# carcomputer_split1.net
KiCad netlist of a schematic drawn in EAGLE
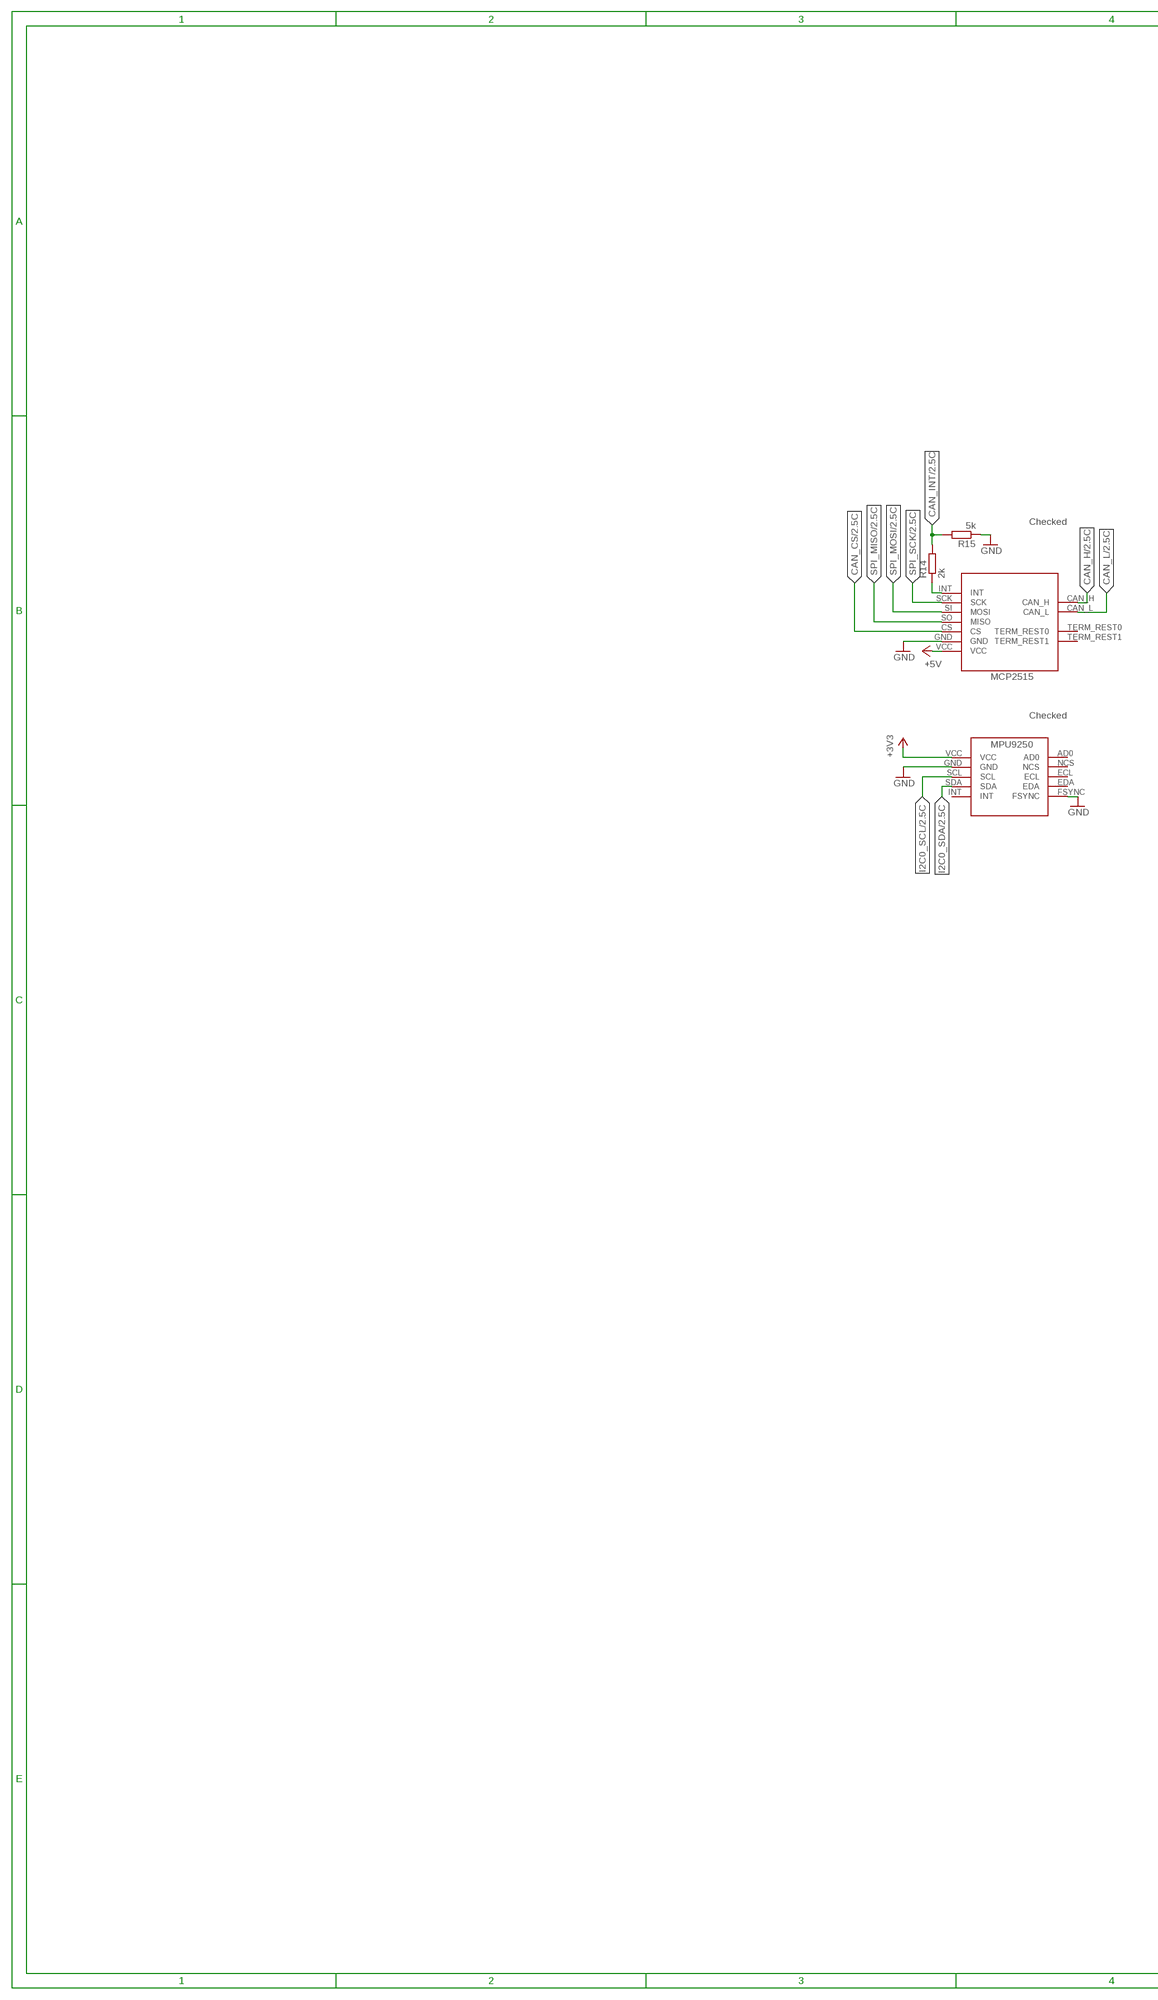
[diagram p0: schematic, sheet 1, part 1 of 2]
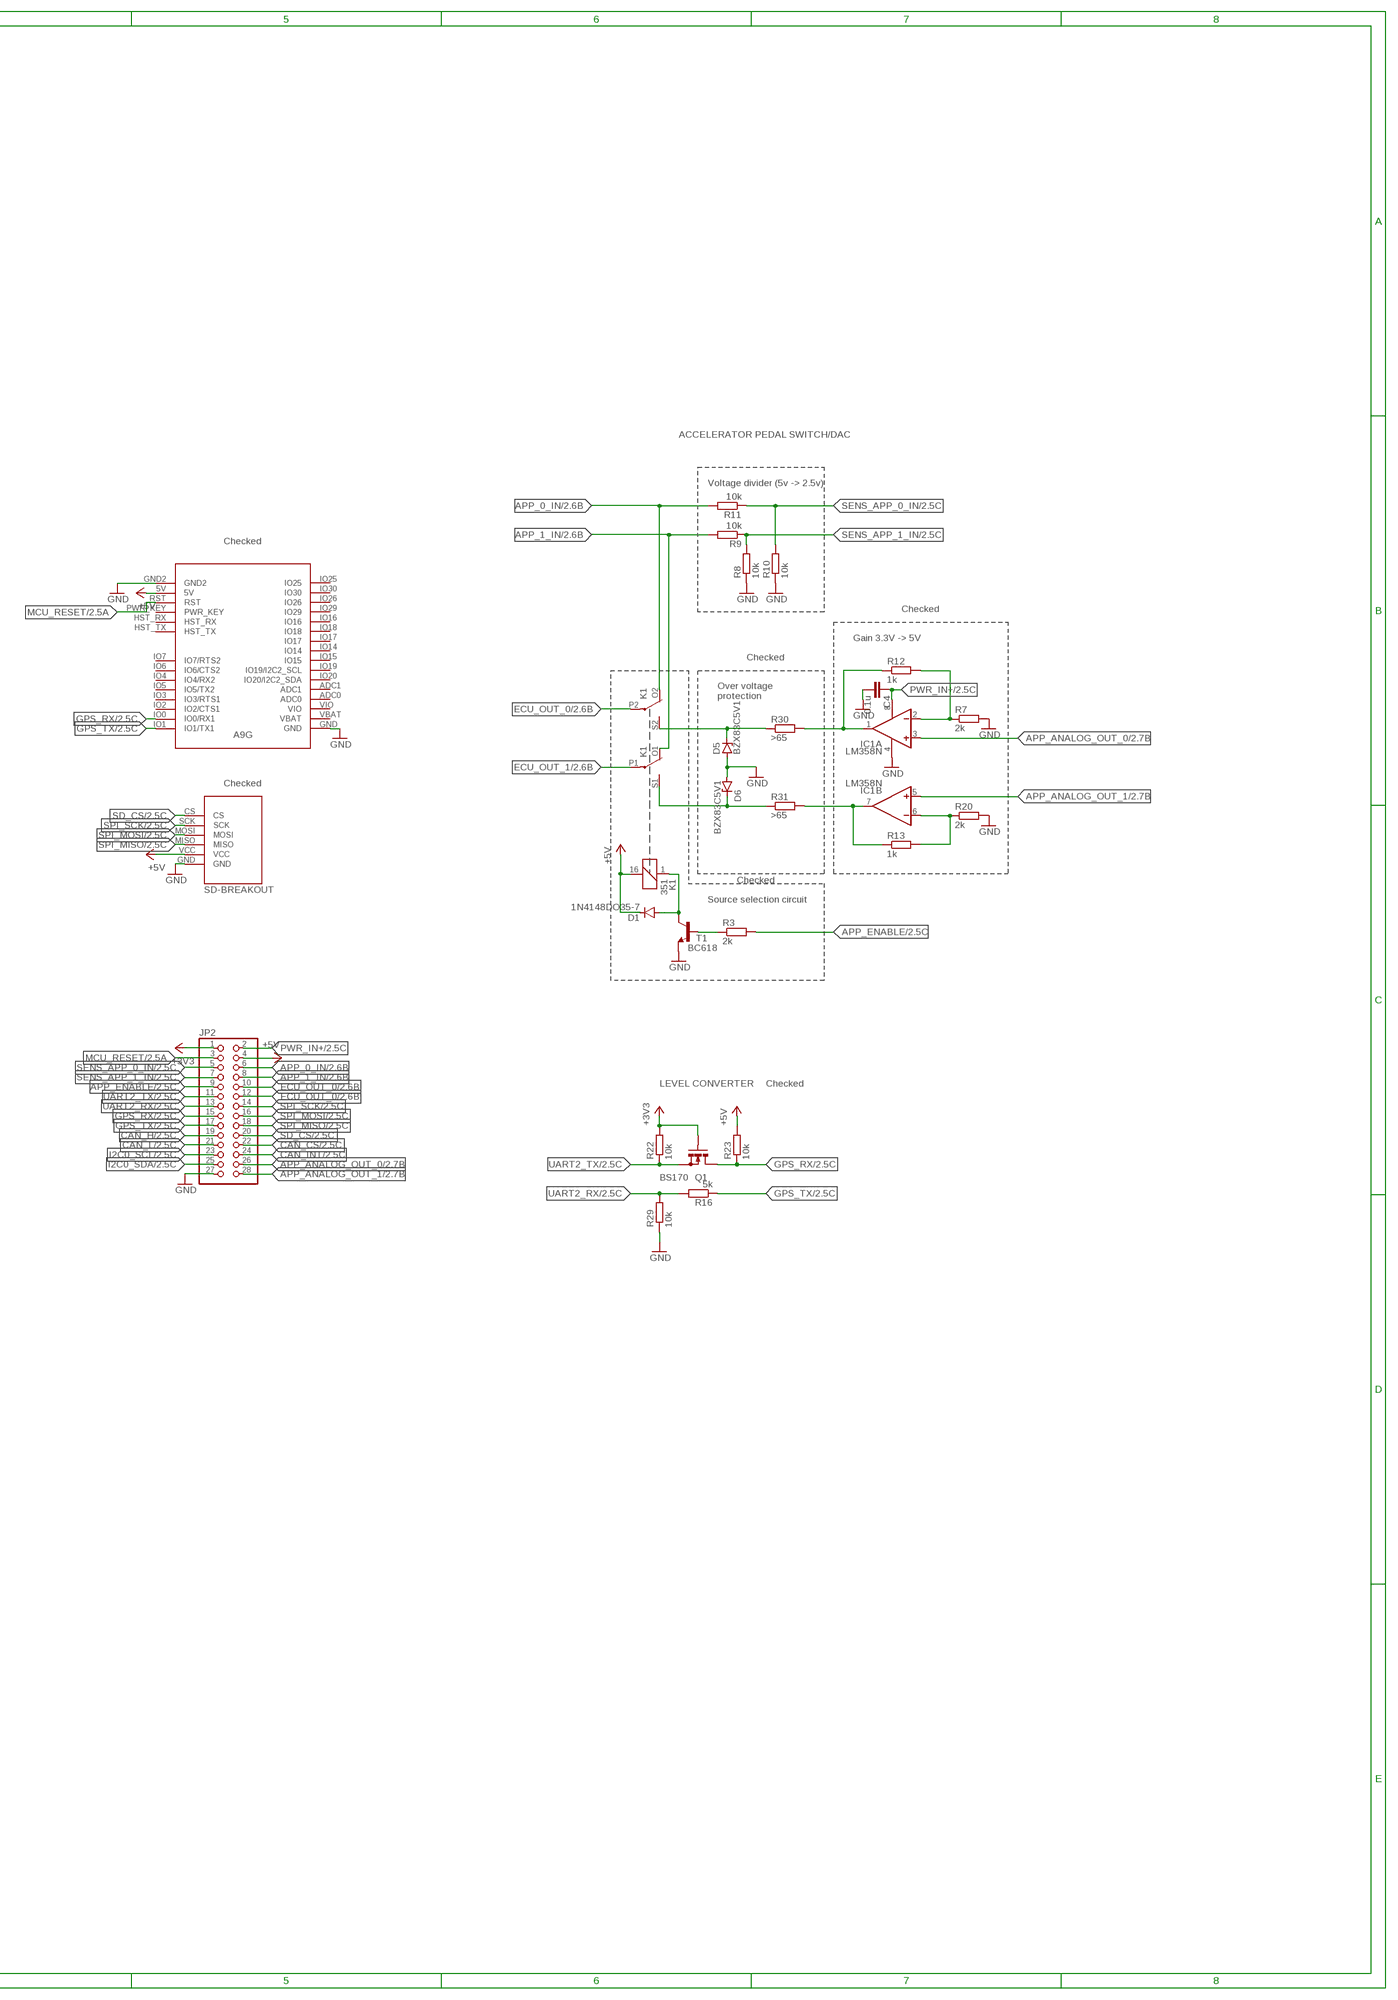
[diagram p1: schematic, sheet 1, part 2 of 2]
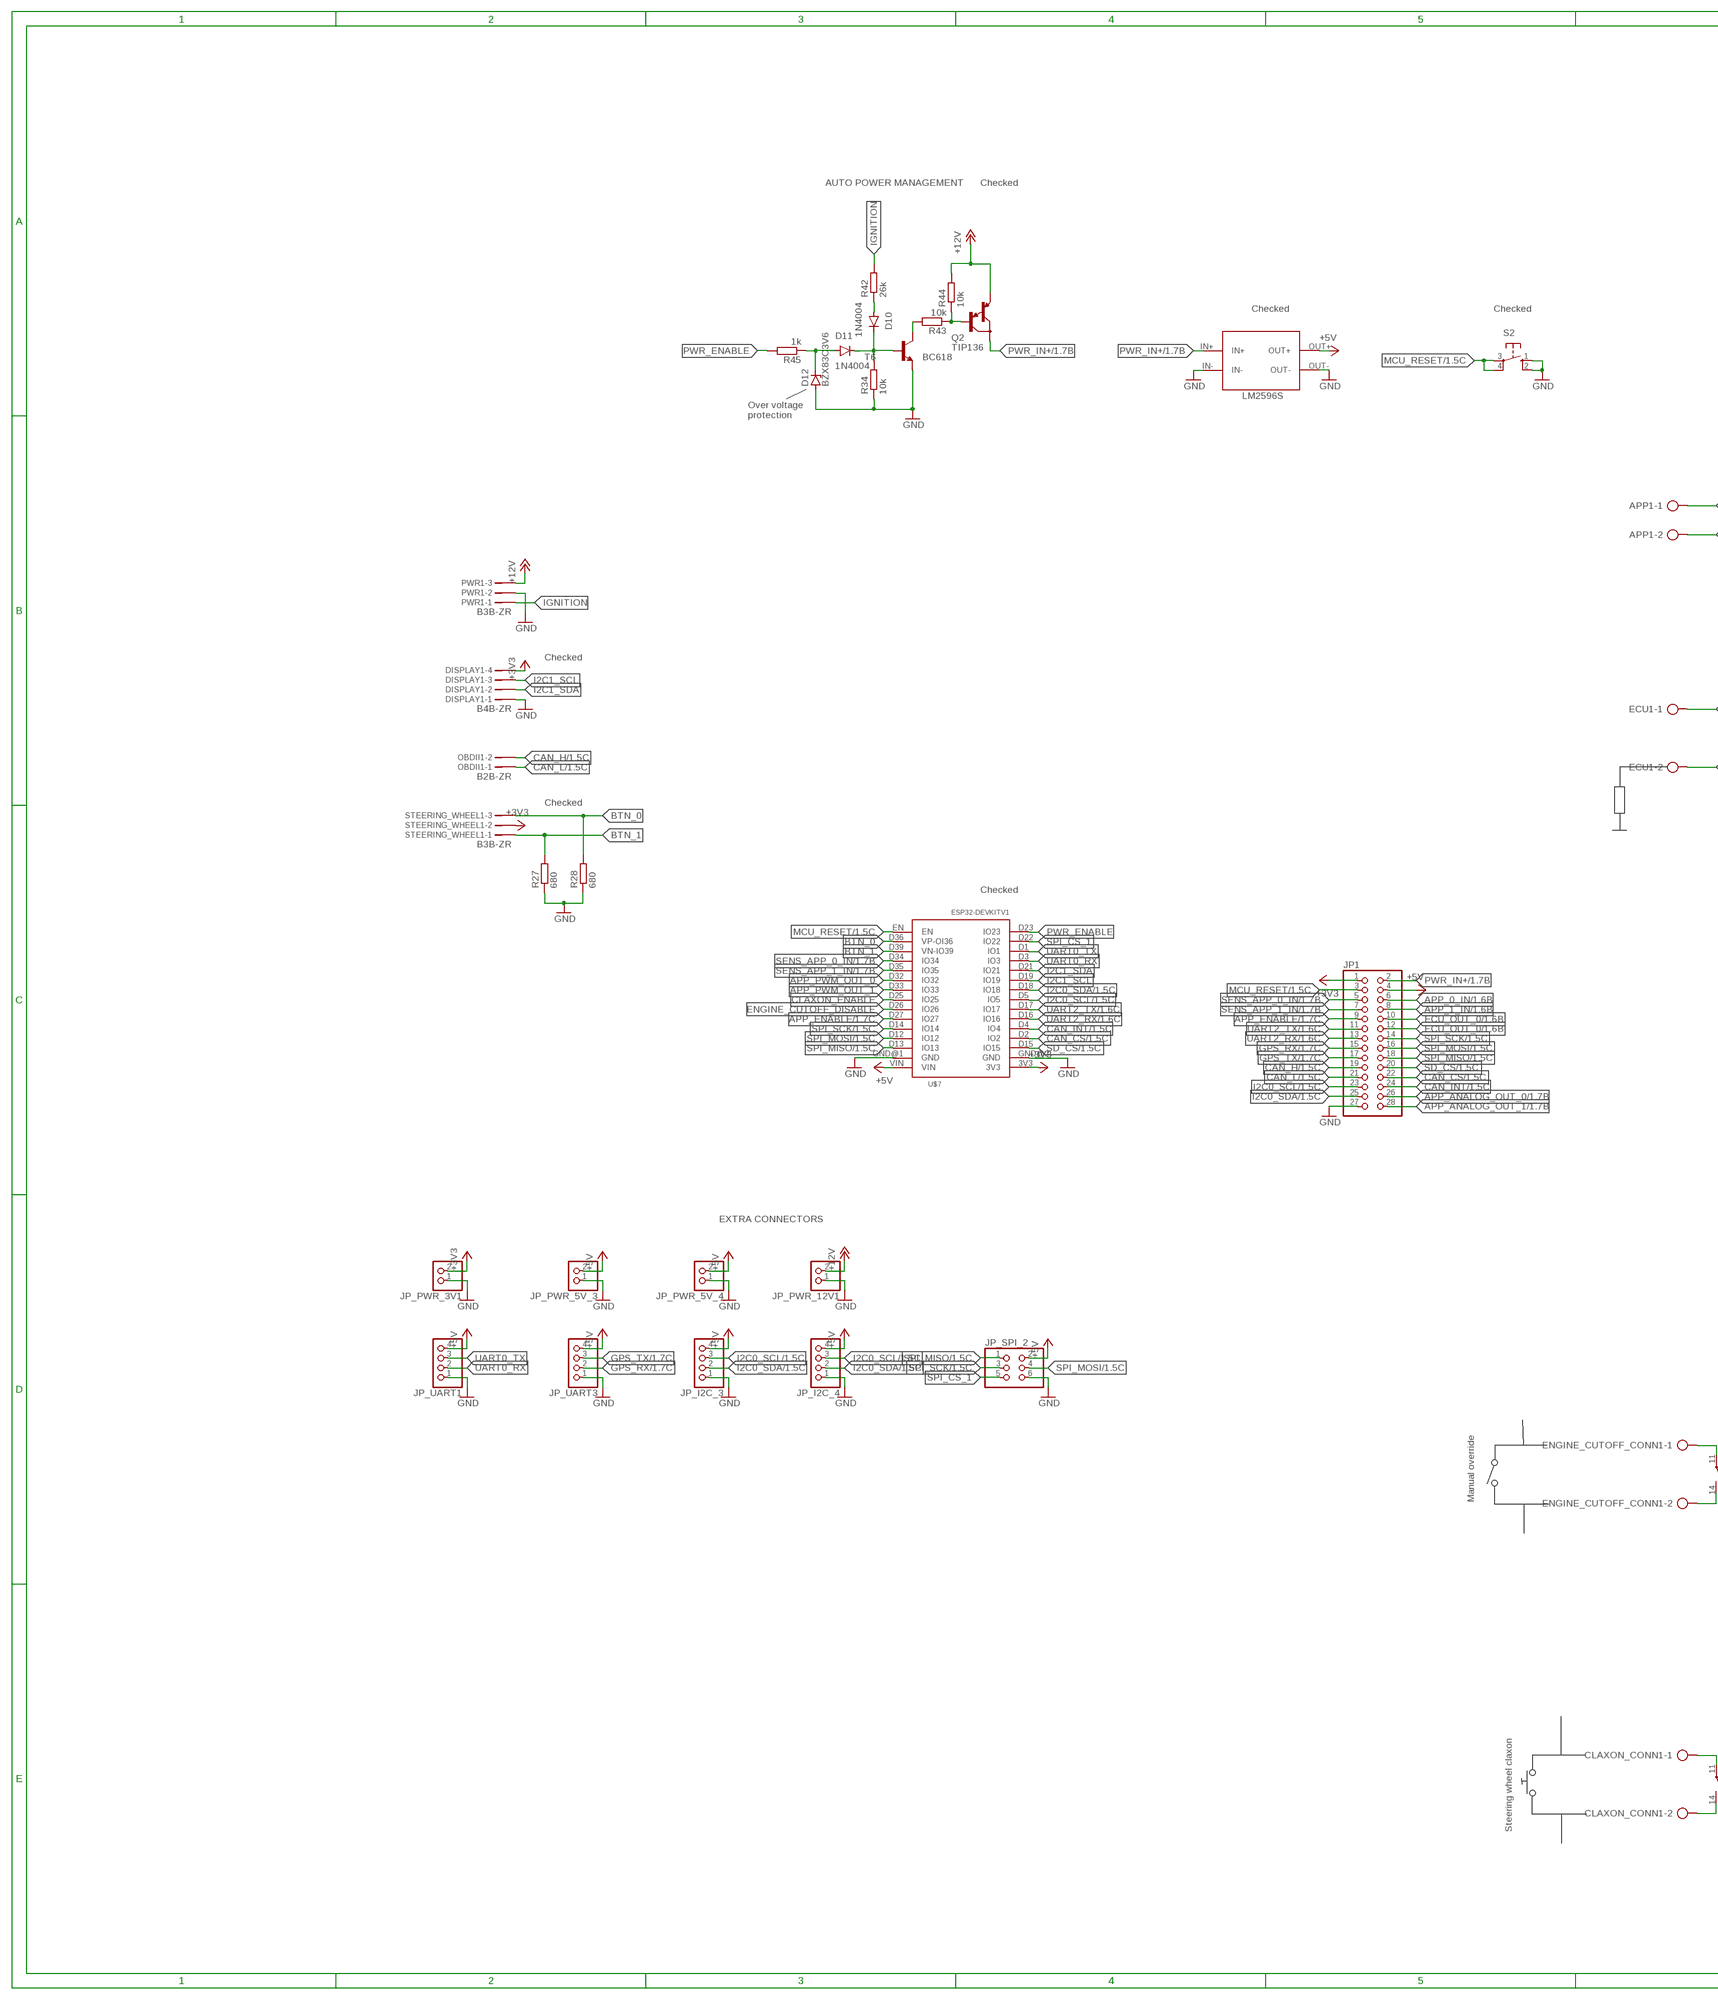
[diagram p2: schematic, sheet 2, part 1 of 2]
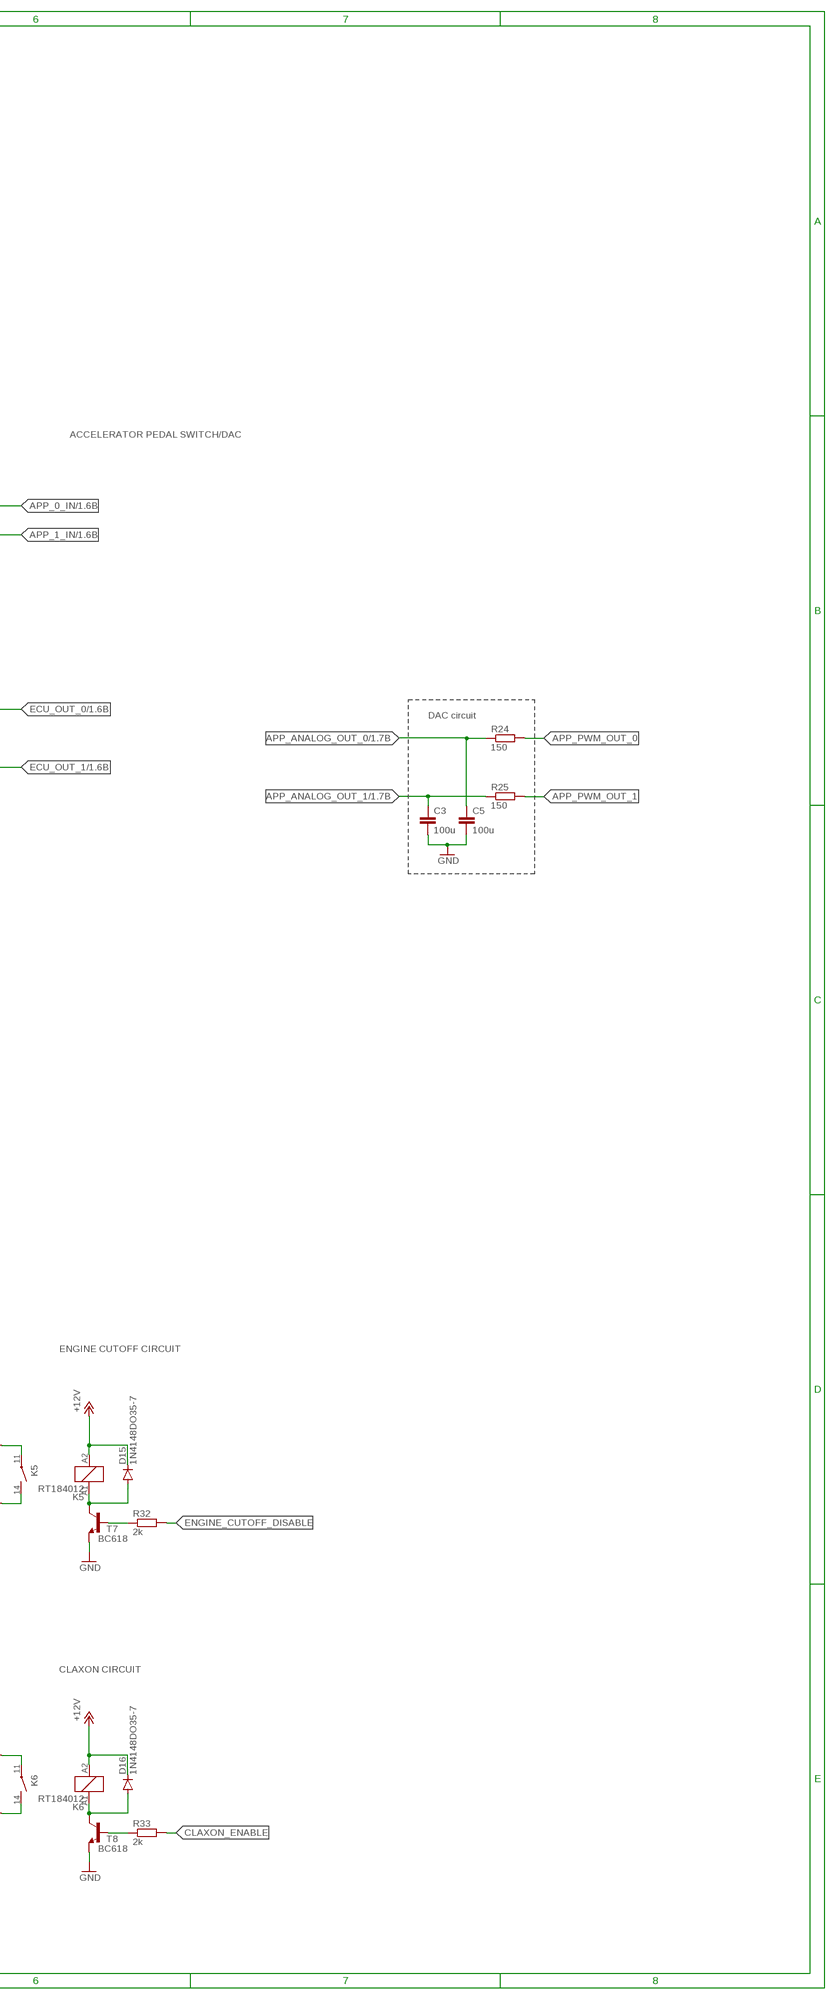
[diagram p3: schematic, sheet 2, part 2 of 2]

(export (version "E")
  (design (tool "Eeschema 10.0.6"))
  (components
    (comp (ref "C4")
      (value "0.1u")
      (footprint "eagle-import:C025-050X050")
      (libsource (lib "eagle-import") (part "C-EU025-050X050"))
    )
    (comp (ref "D1")
      (value "1N4148DO35-7")
      (footprint "eagle-import:DO35-7")
      (libsource (lib "eagle-import") (part "1N4148DO35-7"))
    )
    (comp (ref "D5")
      (value "BZX83C5V1")
      (footprint "eagle-import:DO41Z10")
      (libsource (lib "eagle-import") (part "BZX85"))
    )
    (comp (ref "D6")
      (value "BZX83C5V1")
      (footprint "eagle-import:DO41Z10")
      (libsource (lib "eagle-import") (part "BZX85"))
    )
    (comp (ref "IC1")
      (value "LM358N")
      (footprint "eagle-import:DIL08")
      (libsource (lib "eagle-import") (part "LM358N"))
    )
    (comp (ref "JP2")
      (value "PINHD-2X14")
      (footprint "eagle-import:2X14")
      (libsource (lib "eagle-import") (part "PINHD-2X14"))
    )
    (comp (ref "K1")
      (value "351")
      (footprint "eagle-import:351")
      (libsource (lib "eagle-import") (part "351"))
    )
    (comp (ref "Q1")
      (value "BS170")
      (footprint "eagle-import:SOT54E")
      (libsource (lib "eagle-import") (part "BS170"))
    )
    (comp (ref "R3")
      (value "2k")
      (footprint "eagle-import:0207_7")
      (libsource (lib "eagle-import") (part "R-EU_0207/7"))
    )
    (comp (ref "R7")
      (value "2k")
      (footprint "eagle-import:0207_7")
      (libsource (lib "eagle-import") (part "R-EU_0207/7"))
    )
    (comp (ref "R8")
      (value "10k")
      (footprint "eagle-import:0207_7")
      (libsource (lib "eagle-import") (part "R-EU_0207/7"))
    )
    (comp (ref "R9")
      (value "10k")
      (footprint "eagle-import:0207_7")
      (libsource (lib "eagle-import") (part "R-EU_0207/7"))
    )
    (comp (ref "R10")
      (value "10k")
      (footprint "eagle-import:0207_7")
      (libsource (lib "eagle-import") (part "R-EU_0207/7"))
    )
    (comp (ref "R11")
      (value "10k")
      (footprint "eagle-import:0207_7")
      (libsource (lib "eagle-import") (part "R-EU_0207/7"))
    )
    (comp (ref "R12")
      (value "1k")
      (footprint "eagle-import:0207_7")
      (libsource (lib "eagle-import") (part "R-EU_0207/7"))
    )
    (comp (ref "R13")
      (value "1k")
      (footprint "eagle-import:0207_7")
      (libsource (lib "eagle-import") (part "R-EU_0207/7"))
    )
    (comp (ref "R14")
      (value "2k")
      (footprint "eagle-import:0207_7")
      (libsource (lib "eagle-import") (part "R-EU_0207/7"))
    )
    (comp (ref "R15")
      (value "5k")
      (footprint "eagle-import:0207_7")
      (libsource (lib "eagle-import") (part "R-EU_0207/7"))
    )
    (comp (ref "R16")
      (value "5k")
      (footprint "eagle-import:0207_7")
      (libsource (lib "eagle-import") (part "R-EU_0207/7"))
    )
    (comp (ref "R20")
      (value "2k")
      (footprint "eagle-import:0207_7")
      (libsource (lib "eagle-import") (part "R-EU_0207/7"))
    )
    (comp (ref "R22")
      (value "10k")
      (footprint "eagle-import:0207_7")
      (libsource (lib "eagle-import") (part "R-EU_0207/7"))
    )
    (comp (ref "R23")
      (value "10k")
      (footprint "eagle-import:0207_7")
      (libsource (lib "eagle-import") (part "R-EU_0207/7"))
    )
    (comp (ref "R29")
      (value "10k")
      (footprint "eagle-import:0207_7")
      (libsource (lib "eagle-import") (part "R-EU_0207/7"))
    )
    (comp (ref "R30")
      (value ">65")
      (footprint "eagle-import:0207_7")
      (libsource (lib "eagle-import") (part "R-EU_0207/7"))
    )
    (comp (ref "R31")
      (value ">65")
      (footprint "eagle-import:0207_7")
      (libsource (lib "eagle-import") (part "R-EU_0207/7"))
    )
    (comp (ref "T1")
      (value "BC618")
      (footprint "eagle-import:TO92-EBC")
      (libsource (lib "eagle-import") (part "BC618"))
    )
    (comp (ref "U$2")
      (value "MCP2515_DEVBOARDINVERTED")
      (footprint "eagle-import:MCP2515_DEVBOARD_INVERTED")
      (libsource (lib "eagle-import") (part "MCP2515_DEVBOARDINVERTED"))
    )
    (comp (ref "U$3")
      (value "MPU9250_BREAKOUT")
      (footprint "eagle-import:MPU9250_BREAKOUT")
      (libsource (lib "eagle-import") (part "MPU9250_BREAKOUT"))
    )
    (comp (ref "U$5")
      (value "HKD-MICRO-SD-BREAKOUT")
      (footprint "eagle-import:HKD-MICRO-SD-BREAKOUT")
      (libsource (lib "eagle-import") (part "HKD-MICRO-SD-BREAKOUT"))
    )
    (comp (ref "U$6")
      (value "A9G")
      (footprint "eagle-import:A9G")
      (libsource (lib "eagle-import") (part "A9G"))
    )
    (comp (ref "APP1")
      (value "AK300/2")
      (footprint "eagle-import:AK300_2")
      (libsource (lib "eagle-import") (part "AK300/2"))
    )
    (comp (ref "C3")
      (value "100u")
      (footprint "eagle-import:C025-050X050")
      (libsource (lib "eagle-import") (part "C-EU025-050X050"))
    )
    (comp (ref "C5")
      (value "100u")
      (footprint "eagle-import:C025-050X050")
      (libsource (lib "eagle-import") (part "C-EU025-050X050"))
    )
    (comp (ref "CLAXON_CONN1")
      (value "AK300/2")
      (footprint "eagle-import:AK300_2")
      (libsource (lib "eagle-import") (part "AK300/2"))
    )
    (comp (ref "D10")
      (value "1N4004")
      (footprint "eagle-import:DO41-10")
      (libsource (lib "eagle-import") (part "1N4004"))
    )
    (comp (ref "D11")
      (value "1N4004")
      (footprint "eagle-import:DO41-10")
      (libsource (lib "eagle-import") (part "1N4004"))
    )
    (comp (ref "D12")
      (value "BZX83C3V6")
      (footprint "eagle-import:DO41Z10")
      (libsource (lib "eagle-import") (part "BZX85"))
    )
    (comp (ref "D15")
      (value "1N4148DO35-7")
      (footprint "eagle-import:DO35-7")
      (libsource (lib "eagle-import") (part "1N4148DO35-7"))
    )
    (comp (ref "D16")
      (value "1N4148DO35-7")
      (footprint "eagle-import:DO35-7")
      (libsource (lib "eagle-import") (part "1N4148DO35-7"))
    )
    (comp (ref "DISPLAY1")
      (value "B4B-ZR")
      (footprint "eagle-import:B4B-ZR")
      (fields (field (name "MF") "FARNELL") (field (name "MPN") "B4B-ZR(LF)(SN)"))
      (libsource (lib "eagle-import") (part "?4B-ZRB"))
    )
    (comp (ref "ECU1")
      (value "AK300/2")
      (footprint "eagle-import:AK300_2")
      (libsource (lib "eagle-import") (part "AK300/2"))
    )
    (comp (ref "ENGINE_CUTOFF_CONN1")
      (value "AK300/2")
      (footprint "eagle-import:AK300_2")
      (libsource (lib "eagle-import") (part "AK300/2"))
    )
    (comp (ref "JP1")
      (value "PINHD-2X14")
      (footprint "eagle-import:2X14")
      (libsource (lib "eagle-import") (part "PINHD-2X14"))
    )
    (comp (ref "JP_I2C_3")
      (value "PINHD-1X4")
      (footprint "eagle-import:1X04")
      (libsource (lib "eagle-import") (part "PINHD-1X4"))
    )
    (comp (ref "JP_I2C_4")
      (value "PINHD-1X4")
      (footprint "eagle-import:1X04")
      (libsource (lib "eagle-import") (part "PINHD-1X4"))
    )
    (comp (ref "JP_PWR_3V1")
      (value "PINHD-1X2")
      (footprint "eagle-import:1X02")
      (libsource (lib "eagle-import") (part "PINHD-1X2"))
    )
    (comp (ref "JP_PWR_5V_3")
      (value "PINHD-1X2")
      (footprint "eagle-import:1X02")
      (libsource (lib "eagle-import") (part "PINHD-1X2"))
    )
    (comp (ref "JP_PWR_5V_4")
      (value "PINHD-1X2")
      (footprint "eagle-import:1X02")
      (libsource (lib "eagle-import") (part "PINHD-1X2"))
    )
    (comp (ref "JP_PWR_12V1")
      (value "PINHD-1X2")
      (footprint "eagle-import:1X02")
      (libsource (lib "eagle-import") (part "PINHD-1X2"))
    )
    (comp (ref "JP_SPI_2")
      (value "PINHD-2X3")
      (footprint "eagle-import:2X03")
      (libsource (lib "eagle-import") (part "PINHD-2X3"))
    )
    (comp (ref "JP_UART1")
      (value "PINHD-1X4")
      (footprint "eagle-import:1X04")
      (libsource (lib "eagle-import") (part "PINHD-1X4"))
    )
    (comp (ref "JP_UART3")
      (value "PINHD-1X4")
      (footprint "eagle-import:1X04")
      (libsource (lib "eagle-import") (part "PINHD-1X4"))
    )
    (comp (ref "K5")
      (value "RT184012")
      (footprint "eagle-import:RT-N_O12A3.5")
      (fields (field (name "MF") "TYCO ELECTRONICS"))
      (libsource (lib "eagle-import") (part "RT?184012"))
    )
    (comp (ref "K6")
      (value "RT184012")
      (footprint "eagle-import:RT-N_O12A3.5")
      (fields (field (name "MF") "TYCO ELECTRONICS"))
      (libsource (lib "eagle-import") (part "RT?184012"))
    )
    (comp (ref "OBDII1")
      (value "B2B-ZR")
      (footprint "eagle-import:B2B-ZR")
      (libsource (lib "eagle-import") (part "?2B-ZRB"))
    )
    (comp (ref "PWR1")
      (value "B3B-ZR")
      (footprint "eagle-import:B3B-ZR")
      (libsource (lib "eagle-import") (part "?3B-ZRB"))
    )
    (comp (ref "Q2")
      (value "TIP136")
      (footprint "eagle-import:TO220")
      (libsource (lib "eagle-import") (part "TIP136"))
    )
    (comp (ref "R24")
      (value "150")
      (footprint "eagle-import:0207_7")
      (libsource (lib "eagle-import") (part "R-EU_0207/7"))
    )
    (comp (ref "R25")
      (value "150")
      (footprint "eagle-import:0207_7")
      (libsource (lib "eagle-import") (part "R-EU_0207/7"))
    )
    (comp (ref "R27")
      (value "680")
      (footprint "eagle-import:0207_7")
      (libsource (lib "eagle-import") (part "R-EU_0207/7"))
    )
    (comp (ref "R28")
      (value "680")
      (footprint "eagle-import:0207_7")
      (libsource (lib "eagle-import") (part "R-EU_0207/7"))
    )
    (comp (ref "R32")
      (value "2k")
      (footprint "eagle-import:0207_7")
      (libsource (lib "eagle-import") (part "R-EU_0207/7"))
    )
    (comp (ref "R33")
      (value "2k")
      (footprint "eagle-import:0207_7")
      (libsource (lib "eagle-import") (part "R-EU_0207/7"))
    )
    (comp (ref "R34")
      (value "10k")
      (footprint "eagle-import:0207_7")
      (libsource (lib "eagle-import") (part "R-EU_0207/7"))
    )
    (comp (ref "R42")
      (value "26k")
      (footprint "eagle-import:0207_7")
      (libsource (lib "eagle-import") (part "R-EU_0207/7"))
    )
    (comp (ref "R43")
      (value "10k")
      (footprint "eagle-import:0207_7")
      (libsource (lib "eagle-import") (part "R-EU_0207/7"))
    )
    (comp (ref "R44")
      (value "10k")
      (footprint "eagle-import:0207_7")
      (libsource (lib "eagle-import") (part "R-EU_0207/7"))
    )
    (comp (ref "R45")
      (value "1k")
      (footprint "eagle-import:0207_7")
      (libsource (lib "eagle-import") (part "R-EU_0207/7"))
    )
    (comp (ref "S2")
      (value "10-XX")
      (footprint "eagle-import:B3F-10XX")
      (fields (field (name "MPN") "B3F-1000"))
      (libsource (lib "eagle-import") (part "10-XX"))
    )
    (comp (ref "STEERING_WHEEL1")
      (value "B3B-ZR")
      (footprint "eagle-import:B3B-ZR")
      (libsource (lib "eagle-import") (part "?3B-ZRB"))
    )
    (comp (ref "T6")
      (value "BC618")
      (footprint "eagle-import:TO92-EBC")
      (libsource (lib "eagle-import") (part "BC618"))
    )
    (comp (ref "T7")
      (value "BC618")
      (footprint "eagle-import:TO92-EBC")
      (libsource (lib "eagle-import") (part "BC618"))
    )
    (comp (ref "T8")
      (value "BC618")
      (footprint "eagle-import:TO92-EBC")
      (libsource (lib "eagle-import") (part "BC618"))
    )
    (comp (ref "U$7")
      (value "ESP32DEVKITV1")
      (footprint "eagle-import:ESP32-DEVKITV1")
      (libsource (lib "eagle-import") (part "ESP32DEVKITV1"))
    )
    (comp (ref "U$10")
      (value "LM2596S")
      (footprint "eagle-import:LM2596S")
      (libsource (lib "eagle-import") (part "LM2596S"))
    )
  )
  (nets
    (net (code "1") (name "+3V3") (class "Default")
      (node (ref "DISPLAY1") (pin "4") (pinfunction "1_4") (pintype "passive"))
      (node (ref "JP1") (pin "1") (pinfunction "1_1") (pintype "passive"))
      (node (ref "JP2") (pin "1") (pinfunction "1_1") (pintype "passive"))
      (node (ref "JP_PWR_3V1") (pin "2") (pinfunction "2_2") (pintype "passive"))
      (node (ref "Q1") (pin "G") (pinfunction "G_G") (pintype "passive"))
      (node (ref "R22") (pin "2") (pinfunction "2_2") (pintype "passive"))
      (node (ref "STEERING_WHEEL1") (pin "2") (pinfunction "1_2") (pintype "passive"))
      (node (ref "U$3") (pin "VCC") (pinfunction "VCC_VCC") (pintype "bidirectional"))
      (node (ref "U$7") (pin "3V3") (pinfunction "3V3_3V3") (pintype "bidirectional"))
    )
    (net (code "2") (name "+5V") (class "Default")
      (node (ref "D1") (pin "C") (pinfunction "C_C") (pintype "passive"))
      (node (ref "JP1") (pin "4") (pinfunction "4_4") (pintype "passive"))
      (node (ref "JP2") (pin "4") (pinfunction "4_4") (pintype "passive"))
      (node (ref "JP_I2C_3") (pin "4") (pinfunction "4_4") (pintype "passive"))
      (node (ref "JP_I2C_4") (pin "4") (pinfunction "4_4") (pintype "passive"))
      (node (ref "JP_PWR_5V_3") (pin "2") (pinfunction "2_2") (pintype "passive"))
      (node (ref "JP_PWR_5V_4") (pin "2") (pinfunction "2_2") (pintype "passive"))
      (node (ref "JP_SPI_2") (pin "2") (pinfunction "2_2") (pintype "passive"))
      (node (ref "JP_UART1") (pin "4") (pinfunction "4_4") (pintype "passive"))
      (node (ref "JP_UART3") (pin "4") (pinfunction "4_4") (pintype "passive"))
      (node (ref "K1") (pin "16") (pinfunction "2_16") (pintype "passive"))
      (node (ref "R23") (pin "2") (pinfunction "2_2") (pintype "passive"))
      (node (ref "U$10") (pin "OUT+") (pinfunction "OUT+_OUT+") (pintype "bidirectional"))
      (node (ref "U$2") (pin "VCC") (pinfunction "VCC_VCC") (pintype "bidirectional"))
      (node (ref "U$5") (pin "VCC") (pinfunction "VCC_VCC") (pintype "bidirectional"))
      (node (ref "U$6") (pin "5V") (pinfunction "5V_5V") (pintype "bidirectional"))
      (node (ref "U$7") (pin "VIN") (pinfunction "VIN_VIN") (pintype "bidirectional"))
    )
    (net (code "3") (name "+12V") (class "Default")
      (node (ref "D15") (pin "C") (pinfunction "C_C") (pintype "passive"))
      (node (ref "D16") (pin "C") (pinfunction "C_C") (pintype "passive"))
      (node (ref "JP_PWR_12V1") (pin "2") (pinfunction "2_2") (pintype "passive"))
      (node (ref "K5") (pin "A2") (pinfunction "2_A2") (pintype "passive"))
      (node (ref "K6") (pin "A2") (pinfunction "2_A2") (pintype "passive"))
      (node (ref "PWR1") (pin "3") (pinfunction "1_3") (pintype "passive"))
      (node (ref "Q2") (pin "3") (pinfunction "E_3") (pintype "passive"))
      (node (ref "R44") (pin "2") (pinfunction "2_2") (pintype "passive"))
    )
    (net (code "4") (name "APP_0_IN") (class "Default")
      (node (ref "APP1") (pin "1") (pinfunction "KL_1") (pintype "passive"))
      (node (ref "JP1") (pin "6") (pinfunction "6_6") (pintype "passive"))
      (node (ref "JP2") (pin "6") (pinfunction "6_6") (pintype "passive"))
      (node (ref "K1") (pin "O2") (pinfunction "O_O2") (pintype "passive"))
      (node (ref "R11") (pin "2") (pinfunction "2_2") (pintype "passive"))
    )
    (net (code "5") (name "APP_1_IN") (class "Default")
      (node (ref "APP1") (pin "2") (pinfunction "KL_2") (pintype "passive"))
      (node (ref "JP1") (pin "8") (pinfunction "8_8") (pintype "passive"))
      (node (ref "JP2") (pin "8") (pinfunction "8_8") (pintype "passive"))
      (node (ref "K1") (pin "O1") (pinfunction "O_O1") (pintype "passive"))
      (node (ref "R9") (pin "2") (pinfunction "2_2") (pintype "passive"))
    )
    (net (code "6") (name "APP_ANALOG_OUT_0") (class "Default")
      (node (ref "C5") (pin "1") (pinfunction "1_1") (pintype "passive"))
      (node (ref "IC1") (pin "3") (pinfunction "+IN_3") (pintype "input"))
      (node (ref "JP1") (pin "26") (pinfunction "26_26") (pintype "passive"))
      (node (ref "JP2") (pin "26") (pinfunction "26_26") (pintype "passive"))
      (node (ref "R24") (pin "1") (pinfunction "1_1") (pintype "passive"))
    )
    (net (code "7") (name "APP_ANALOG_OUT_1") (class "Default")
      (node (ref "C3") (pin "1") (pinfunction "1_1") (pintype "passive"))
      (node (ref "IC1") (pin "5") (pinfunction "+IN_5") (pintype "input"))
      (node (ref "JP1") (pin "28") (pinfunction "28_28") (pintype "passive"))
      (node (ref "JP2") (pin "28") (pinfunction "28_28") (pintype "passive"))
      (node (ref "R25") (pin "1") (pinfunction "1_1") (pintype "passive"))
    )
    (net (code "8") (name "APP_ENABLE") (class "Default")
      (node (ref "JP1") (pin "9") (pinfunction "9_9") (pintype "passive"))
      (node (ref "JP2") (pin "9") (pinfunction "9_9") (pintype "passive"))
      (node (ref "R3") (pin "2") (pinfunction "2_2") (pintype "passive"))
      (node (ref "U$7") (pin "D27") (pinfunction "IO27_D27") (pintype "bidirectional"))
    )
    (net (code "9") (name "APP_PWM_OUT_0") (class "Default")
      (node (ref "R24") (pin "2") (pinfunction "2_2") (pintype "passive"))
      (node (ref "U$7") (pin "D32") (pinfunction "IO32_D32") (pintype "bidirectional"))
    )
    (net (code "10") (name "APP_PWM_OUT_1") (class "Default")
      (node (ref "R25") (pin "2") (pinfunction "2_2") (pintype "passive"))
      (node (ref "U$7") (pin "D33") (pinfunction "IO33_D33") (pintype "bidirectional"))
    )
    (net (code "11") (name "BTN_0") (class "Default")
      (node (ref "R28") (pin "2") (pinfunction "2_2") (pintype "passive"))
      (node (ref "STEERING_WHEEL1") (pin "3") (pinfunction "1_3") (pintype "passive"))
      (node (ref "U$7") (pin "D36") (pinfunction "VP-OI36_D36") (pintype "bidirectional"))
    )
    (net (code "12") (name "BTN_1") (class "Default")
      (node (ref "R27") (pin "2") (pinfunction "2_2") (pintype "passive"))
      (node (ref "STEERING_WHEEL1") (pin "1") (pinfunction "1_1") (pintype "passive"))
      (node (ref "U$7") (pin "D39") (pinfunction "VN-IO39_D39") (pintype "bidirectional"))
    )
    (net (code "13") (name "CAN_CS") (class "Default")
      (node (ref "JP1") (pin "22") (pinfunction "22_22") (pintype "passive"))
      (node (ref "JP2") (pin "22") (pinfunction "22_22") (pintype "passive"))
      (node (ref "U$2") (pin "CS") (pinfunction "CS_CS") (pintype "input"))
      (node (ref "U$7") (pin "D2") (pinfunction "IO2_D2") (pintype "bidirectional"))
    )
    (net (code "14") (name "CAN_H") (class "Default")
      (node (ref "JP1") (pin "19") (pinfunction "19_19") (pintype "passive"))
      (node (ref "JP2") (pin "19") (pinfunction "19_19") (pintype "passive"))
      (node (ref "OBDII1") (pin "2") (pinfunction "1_2") (pintype "passive"))
      (node (ref "U$2") (pin "CAN_H") (pinfunction "CAN_H_CAN_H") (pintype "bidirectional"))
    )
    (net (code "15") (name "CAN_INT") (class "Default")
      (node (ref "JP1") (pin "24") (pinfunction "24_24") (pintype "passive"))
      (node (ref "JP2") (pin "24") (pinfunction "24_24") (pintype "passive"))
      (node (ref "R14") (pin "2") (pinfunction "2_2") (pintype "passive"))
      (node (ref "R15") (pin "2") (pinfunction "2_2") (pintype "passive"))
      (node (ref "U$7") (pin "D4") (pinfunction "IO4_D4") (pintype "bidirectional"))
    )
    (net (code "16") (name "CAN_L") (class "Default")
      (node (ref "JP1") (pin "21") (pinfunction "21_21") (pintype "passive"))
      (node (ref "JP2") (pin "21") (pinfunction "21_21") (pintype "passive"))
      (node (ref "OBDII1") (pin "1") (pinfunction "1_1") (pintype "passive"))
      (node (ref "U$2") (pin "CAN_L") (pinfunction "CAN_L_CAN_L") (pintype "bidirectional"))
    )
    (net (code "17") (name "CLAXON_ENABLE") (class "Default")
      (node (ref "R33") (pin "2") (pinfunction "2_2") (pintype "passive"))
      (node (ref "U$7") (pin "D25") (pinfunction "IO25_D25") (pintype "bidirectional"))
    )
    (net (code "18") (name "ECU_OUT_0") (class "Default")
      (node (ref "ECU1") (pin "1") (pinfunction "KL_1") (pintype "passive"))
      (node (ref "JP1") (pin "10") (pinfunction "10_10") (pintype "passive"))
      (node (ref "JP1") (pin "12") (pinfunction "12_12") (pintype "passive"))
      (node (ref "JP2") (pin "10") (pinfunction "10_10") (pintype "passive"))
      (node (ref "JP2") (pin "12") (pinfunction "12_12") (pintype "passive"))
      (node (ref "K1") (pin "P2") (pinfunction "P_P2") (pintype "passive"))
    )
    (net (code "19") (name "ECU_OUT_1") (class "Default")
      (node (ref "ECU1") (pin "2") (pinfunction "KL_2") (pintype "passive"))
      (node (ref "K1") (pin "P1") (pinfunction "P_P1") (pintype "passive"))
    )
    (net (code "20") (name "ENGINE_CUTOFF_DISABLE") (class "Default")
      (node (ref "R32") (pin "2") (pinfunction "2_2") (pintype "passive"))
      (node (ref "U$7") (pin "D26") (pinfunction "IO26_D26") (pintype "bidirectional"))
    )
    (net (code "21") (name "GND") (class "Default")
      (node (ref "C3") (pin "2") (pinfunction "2_2") (pintype "passive"))
      (node (ref "C4") (pin "2") (pinfunction "2_2") (pintype "passive"))
      (node (ref "C5") (pin "2") (pinfunction "2_2") (pintype "passive"))
      (node (ref "D12") (pin "A") (pinfunction "A_A") (pintype "passive"))
      (node (ref "D5") (pin "A") (pinfunction "A_A") (pintype "passive"))
      (node (ref "D6") (pin "A") (pinfunction "A_A") (pintype "passive"))
      (node (ref "DISPLAY1") (pin "1") (pinfunction "1_1") (pintype "passive"))
      (node (ref "IC1") (pin "4") (pinfunction "V-_4") (pintype "power_in"))
      (node (ref "JP1") (pin "27") (pinfunction "27_27") (pintype "passive"))
      (node (ref "JP2") (pin "27") (pinfunction "27_27") (pintype "passive"))
      (node (ref "JP_I2C_3") (pin "1") (pinfunction "1_1") (pintype "passive"))
      (node (ref "JP_I2C_4") (pin "1") (pinfunction "1_1") (pintype "passive"))
      (node (ref "JP_PWR_12V1") (pin "1") (pinfunction "1_1") (pintype "passive"))
      (node (ref "JP_PWR_3V1") (pin "1") (pinfunction "1_1") (pintype "passive"))
      (node (ref "JP_PWR_5V_3") (pin "1") (pinfunction "1_1") (pintype "passive"))
      (node (ref "JP_PWR_5V_4") (pin "1") (pinfunction "1_1") (pintype "passive"))
      (node (ref "JP_SPI_2") (pin "6") (pinfunction "6_6") (pintype "passive"))
      (node (ref "JP_UART1") (pin "1") (pinfunction "1_1") (pintype "passive"))
      (node (ref "JP_UART3") (pin "1") (pinfunction "1_1") (pintype "passive"))
      (node (ref "PWR1") (pin "2") (pinfunction "1_2") (pintype "passive"))
      (node (ref "R10") (pin "1") (pinfunction "1_1") (pintype "passive"))
      (node (ref "R15") (pin "1") (pinfunction "1_1") (pintype "passive"))
      (node (ref "R20") (pin "2") (pinfunction "2_2") (pintype "passive"))
      (node (ref "R27") (pin "1") (pinfunction "1_1") (pintype "passive"))
      (node (ref "R28") (pin "1") (pinfunction "1_1") (pintype "passive"))
      (node (ref "R29") (pin "1") (pinfunction "1_1") (pintype "passive"))
      (node (ref "R34") (pin "1") (pinfunction "1_1") (pintype "passive"))
      (node (ref "R7") (pin "2") (pinfunction "2_2") (pintype "passive"))
      (node (ref "R8") (pin "1") (pinfunction "1_1") (pintype "passive"))
      (node (ref "S2") (pin "1") (pinfunction "S_1") (pintype "passive"))
      (node (ref "S2") (pin "2") (pinfunction "S1_2") (pintype "passive"))
      (node (ref "T1") (pin "E") (pinfunction "E_E") (pintype "passive"))
      (node (ref "T6") (pin "E") (pinfunction "E_E") (pintype "passive"))
      (node (ref "T7") (pin "E") (pinfunction "E_E") (pintype "passive"))
      (node (ref "T8") (pin "E") (pinfunction "E_E") (pintype "passive"))
      (node (ref "U$10") (pin "IN-") (pinfunction "IN-_IN-") (pintype "bidirectional"))
      (node (ref "U$10") (pin "OUT-") (pinfunction "OUT-_OUT-") (pintype "bidirectional"))
      (node (ref "U$2") (pin "GND") (pinfunction "GND_GND") (pintype "bidirectional"))
      (node (ref "U$3") (pin "FSYNC") (pinfunction "FSYNC_FSYNC") (pintype "bidirectional"))
      (node (ref "U$3") (pin "GND") (pinfunction "GND_GND") (pintype "bidirectional"))
      (node (ref "U$5") (pin "GND") (pinfunction "GND_GND") (pintype "bidirectional"))
      (node (ref "U$6") (pin "GND") (pinfunction "GND_GND") (pintype "bidirectional"))
      (node (ref "U$6") (pin "GND2") (pinfunction "GND2_GND2") (pintype "bidirectional"))
      (node (ref "U$7") (pin "GND@1") (pinfunction "GND_GND@1") (pintype "bidirectional"))
      (node (ref "U$7") (pin "GND@2") (pinfunction "GND_GND@2") (pintype "bidirectional"))
    )
    (net (code "22") (name "GPS_RX") (class "Default")
      (node (ref "JP1") (pin "15") (pinfunction "15_15") (pintype "passive"))
      (node (ref "JP2") (pin "15") (pinfunction "15_15") (pintype "passive"))
      (node (ref "JP_UART3") (pin "2") (pinfunction "2_2") (pintype "passive"))
      (node (ref "Q1") (pin "D") (pinfunction "D_D") (pintype "passive"))
      (node (ref "R23") (pin "1") (pinfunction "1_1") (pintype "passive"))
      (node (ref "U$6") (pin "IO0") (pinfunction "IO0/RX1_IO0") (pintype "bidirectional"))
    )
    (net (code "23") (name "GPS_TX") (class "Default")
      (node (ref "JP1") (pin "17") (pinfunction "17_17") (pintype "passive"))
      (node (ref "JP2") (pin "17") (pinfunction "17_17") (pintype "passive"))
      (node (ref "JP_UART3") (pin "3") (pinfunction "3_3") (pintype "passive"))
      (node (ref "R16") (pin "1") (pinfunction "1_1") (pintype "passive"))
      (node (ref "U$6") (pin "IO1") (pinfunction "IO1/TX1_IO1") (pintype "bidirectional"))
    )
    (net (code "24") (name "I2C0_SCL") (class "Default")
      (node (ref "JP1") (pin "23") (pinfunction "23_23") (pintype "passive"))
      (node (ref "JP2") (pin "23") (pinfunction "23_23") (pintype "passive"))
      (node (ref "JP_I2C_3") (pin "3") (pinfunction "3_3") (pintype "passive"))
      (node (ref "JP_I2C_4") (pin "3") (pinfunction "3_3") (pintype "passive"))
      (node (ref "U$3") (pin "SCL") (pinfunction "SCL_SCL") (pintype "bidirectional"))
      (node (ref "U$7") (pin "D5") (pinfunction "IO5_D5") (pintype "bidirectional"))
    )
    (net (code "25") (name "I2C0_SDA") (class "Default")
      (node (ref "JP1") (pin "25") (pinfunction "25_25") (pintype "passive"))
      (node (ref "JP2") (pin "25") (pinfunction "25_25") (pintype "passive"))
      (node (ref "JP_I2C_3") (pin "2") (pinfunction "2_2") (pintype "passive"))
      (node (ref "JP_I2C_4") (pin "2") (pinfunction "2_2") (pintype "passive"))
      (node (ref "U$3") (pin "SDA") (pinfunction "SDA_SDA") (pintype "bidirectional"))
      (node (ref "U$7") (pin "D18") (pinfunction "IO18_D18") (pintype "bidirectional"))
    )
    (net (code "26") (name "I2C1_SCL") (class "Default")
      (node (ref "DISPLAY1") (pin "3") (pinfunction "1_3") (pintype "passive"))
      (node (ref "U$7") (pin "D19") (pinfunction "IO19_D19") (pintype "bidirectional"))
    )
    (net (code "27") (name "I2C1_SDA") (class "Default")
      (node (ref "DISPLAY1") (pin "2") (pinfunction "1_2") (pintype "passive"))
      (node (ref "U$7") (pin "D21") (pinfunction "IO21_D21") (pintype "bidirectional"))
    )
    (net (code "28") (name "IGNITION") (class "Default")
      (node (ref "PWR1") (pin "1") (pinfunction "1_1") (pintype "passive"))
      (node (ref "R42") (pin "2") (pinfunction "2_2") (pintype "passive"))
    )
    (net (code "29") (name "MCU_RESET") (class "Default")
      (node (ref "JP1") (pin "3") (pinfunction "3_3") (pintype "passive"))
      (node (ref "JP2") (pin "3") (pinfunction "3_3") (pintype "passive"))
      (node (ref "S2") (pin "3") (pinfunction "P_3") (pintype "passive"))
      (node (ref "S2") (pin "4") (pinfunction "P1_4") (pintype "passive"))
      (node (ref "U$6") (pin "RST") (pinfunction "RST_RST") (pintype "bidirectional"))
      (node (ref "U$7") (pin "EN") (pinfunction "EN_EN") (pintype "bidirectional"))
    )
    (net (code "30") (name "Net-(CLAXON_CONN1A-KL)") (class "Default")
      (node (ref "CLAXON_CONN1") (pin "1") (pinfunction "KL_1") (pintype "passive"))
      (node (ref "K6") (pin "11") (pinfunction "P_11") (pintype "passive"))
    )
    (net (code "31") (name "Net-(CLAXON_CONN1B-KL)") (class "Default")
      (node (ref "CLAXON_CONN1") (pin "2") (pinfunction "KL_2") (pintype "passive"))
      (node (ref "K6") (pin "14") (pinfunction "S_14") (pintype "passive"))
    )
    (net (code "32") (name "Net-(D1-PadA)") (class "Default")
      (node (ref "D1") (pin "A") (pinfunction "A_A") (pintype "passive"))
      (node (ref "K1") (pin "1") (pinfunction "1_1") (pintype "passive"))
      (node (ref "T1") (pin "C") (pinfunction "C_C") (pintype "passive"))
    )
    (net (code "33") (name "Net-(D10-PadA)") (class "Default")
      (node (ref "D10") (pin "A") (pinfunction "A_A") (pintype "passive"))
      (node (ref "R42") (pin "1") (pinfunction "1_1") (pintype "passive"))
    )
    (net (code "34") (name "Net-(D10-PadC)") (class "Default")
      (node (ref "D10") (pin "C") (pinfunction "C_C") (pintype "passive"))
      (node (ref "D11") (pin "C") (pinfunction "C_C") (pintype "passive"))
      (node (ref "R34") (pin "2") (pinfunction "2_2") (pintype "passive"))
      (node (ref "T6") (pin "B") (pinfunction "B_B") (pintype "passive"))
    )
    (net (code "35") (name "Net-(D11-PadA)") (class "Default")
      (node (ref "D11") (pin "A") (pinfunction "A_A") (pintype "passive"))
      (node (ref "D12") (pin "C") (pinfunction "C_C") (pintype "passive"))
      (node (ref "R45") (pin "1") (pinfunction "1_1") (pintype "passive"))
    )
    (net (code "36") (name "Net-(ENGINE_CUTOFF_CONN1A-KL)") (class "Default")
      (node (ref "ENGINE_CUTOFF_CONN1") (pin "1") (pinfunction "KL_1") (pintype "passive"))
      (node (ref "K5") (pin "11") (pinfunction "P_11") (pintype "passive"))
    )
    (net (code "37") (name "Net-(ENGINE_CUTOFF_CONN1B-KL)") (class "Default")
      (node (ref "ENGINE_CUTOFF_CONN1") (pin "2") (pinfunction "KL_2") (pintype "passive"))
      (node (ref "K5") (pin "14") (pinfunction "S_14") (pintype "passive"))
    )
    (net (code "38") (name "Net-(IC1A--IN)") (class "Default")
      (node (ref "IC1") (pin "2") (pinfunction "-IN_2") (pintype "input"))
      (node (ref "R12") (pin "2") (pinfunction "2_2") (pintype "passive"))
      (node (ref "R7") (pin "1") (pinfunction "1_1") (pintype "passive"))
    )
    (net (code "39") (name "Net-(IC1A-OUT)") (class "Default")
      (node (ref "IC1") (pin "1") (pinfunction "OUT_1") (pintype "output"))
      (node (ref "R12") (pin "1") (pinfunction "1_1") (pintype "passive"))
      (node (ref "R30") (pin "2") (pinfunction "2_2") (pintype "passive"))
    )
    (net (code "40") (name "Net-(IC1B--IN)") (class "Default")
      (node (ref "IC1") (pin "6") (pinfunction "-IN_6") (pintype "input"))
      (node (ref "R13") (pin "2") (pinfunction "2_2") (pintype "passive"))
      (node (ref "R20") (pin "1") (pinfunction "1_1") (pintype "passive"))
    )
    (net (code "41") (name "Net-(IC1B-OUT)") (class "Default")
      (node (ref "IC1") (pin "7") (pinfunction "OUT_7") (pintype "output"))
      (node (ref "R13") (pin "1") (pinfunction "1_1") (pintype "passive"))
      (node (ref "R31") (pin "2") (pinfunction "2_2") (pintype "passive"))
    )
    (net (code "42") (name "Net-(K1B-S)") (class "Default")
      (node (ref "D6") (pin "C") (pinfunction "C_C") (pintype "passive"))
      (node (ref "K1") (pin "S1") (pinfunction "S_S1") (pintype "passive"))
      (node (ref "R31") (pin "1") (pinfunction "1_1") (pintype "passive"))
    )
    (net (code "43") (name "Net-(K1C-S)") (class "Default")
      (node (ref "D5") (pin "C") (pinfunction "C_C") (pintype "passive"))
      (node (ref "K1") (pin "S2") (pinfunction "S_S2") (pintype "passive"))
      (node (ref "R30") (pin "1") (pinfunction "1_1") (pintype "passive"))
    )
    (net (code "44") (name "Net-(K5A-1)") (class "Default")
      (node (ref "D15") (pin "A") (pinfunction "A_A") (pintype "passive"))
      (node (ref "K5") (pin "A1") (pinfunction "1_A1") (pintype "passive"))
      (node (ref "T7") (pin "C") (pinfunction "C_C") (pintype "passive"))
    )
    (net (code "45") (name "Net-(K6A-1)") (class "Default")
      (node (ref "D16") (pin "A") (pinfunction "A_A") (pintype "passive"))
      (node (ref "K6") (pin "A1") (pinfunction "1_A1") (pintype "passive"))
      (node (ref "T8") (pin "C") (pinfunction "C_C") (pintype "passive"))
    )
    (net (code "46") (name "Net-(Q2-B)") (class "Default")
      (node (ref "Q2") (pin "1") (pinfunction "B_1") (pintype "passive"))
      (node (ref "R43") (pin "1") (pinfunction "1_1") (pintype "passive"))
      (node (ref "R44") (pin "1") (pinfunction "1_1") (pintype "passive"))
    )
    (net (code "47") (name "Net-(R3-Pad1)") (class "Default")
      (node (ref "R3") (pin "1") (pinfunction "1_1") (pintype "passive"))
      (node (ref "T1") (pin "B") (pinfunction "B_B") (pintype "passive"))
    )
    (net (code "48") (name "Net-(R14-Pad1)") (class "Default")
      (node (ref "R14") (pin "1") (pinfunction "1_1") (pintype "passive"))
      (node (ref "U$2") (pin "INT") (pinfunction "INT_INT") (pintype "output"))
    )
    (net (code "49") (name "Net-(R32-Pad1)") (class "Default")
      (node (ref "R32") (pin "1") (pinfunction "1_1") (pintype "passive"))
      (node (ref "T7") (pin "B") (pinfunction "B_B") (pintype "passive"))
    )
    (net (code "50") (name "Net-(R33-Pad1)") (class "Default")
      (node (ref "R33") (pin "1") (pinfunction "1_1") (pintype "passive"))
      (node (ref "T8") (pin "B") (pinfunction "B_B") (pintype "passive"))
    )
    (net (code "51") (name "Net-(R43-Pad2)") (class "Default")
      (node (ref "R43") (pin "2") (pinfunction "2_2") (pintype "passive"))
      (node (ref "T6") (pin "C") (pinfunction "C_C") (pintype "passive"))
    )
    (net (code "52") (name "PWR_ENABLE") (class "Default")
      (node (ref "R45") (pin "2") (pinfunction "2_2") (pintype "passive"))
      (node (ref "U$7") (pin "D23") (pinfunction "IO23_D23") (pintype "bidirectional"))
    )
    (net (code "53") (name "PWR_IN+") (class "Default")
      (node (ref "C4") (pin "1") (pinfunction "1_1") (pintype "passive"))
      (node (ref "IC1") (pin "8") (pinfunction "V+_8") (pintype "power_in"))
      (node (ref "JP1") (pin "2") (pinfunction "2_2") (pintype "passive"))
      (node (ref "JP2") (pin "2") (pinfunction "2_2") (pintype "passive"))
      (node (ref "Q2") (pin "2") (pinfunction "C_2") (pintype "passive"))
      (node (ref "U$10") (pin "IN+") (pinfunction "IN+_IN+") (pintype "bidirectional"))
    )
    (net (code "54") (name "SD_CS") (class "Default")
      (node (ref "JP1") (pin "20") (pinfunction "20_20") (pintype "passive"))
      (node (ref "JP2") (pin "20") (pinfunction "20_20") (pintype "passive"))
      (node (ref "U$5") (pin "CS") (pinfunction "CS_CS") (pintype "bidirectional"))
      (node (ref "U$7") (pin "D15") (pinfunction "IO15_D15") (pintype "bidirectional"))
    )
    (net (code "55") (name "SENS_APP_0_IN") (class "Default")
      (node (ref "JP1") (pin "5") (pinfunction "5_5") (pintype "passive"))
      (node (ref "JP2") (pin "5") (pinfunction "5_5") (pintype "passive"))
      (node (ref "R10") (pin "2") (pinfunction "2_2") (pintype "passive"))
      (node (ref "R11") (pin "1") (pinfunction "1_1") (pintype "passive"))
      (node (ref "U$7") (pin "D34") (pinfunction "IO34_D34") (pintype "bidirectional"))
    )
    (net (code "56") (name "SENS_APP_1_IN") (class "Default")
      (node (ref "JP1") (pin "7") (pinfunction "7_7") (pintype "passive"))
      (node (ref "JP2") (pin "7") (pinfunction "7_7") (pintype "passive"))
      (node (ref "R8") (pin "2") (pinfunction "2_2") (pintype "passive"))
      (node (ref "R9") (pin "1") (pinfunction "1_1") (pintype "passive"))
      (node (ref "U$7") (pin "D35") (pinfunction "IO35_D35") (pintype "bidirectional"))
    )
    (net (code "57") (name "SPI_CS_1") (class "Default")
      (node (ref "JP_SPI_2") (pin "5") (pinfunction "5_5") (pintype "passive"))
      (node (ref "U$7") (pin "D22") (pinfunction "IO22_D22") (pintype "bidirectional"))
    )
    (net (code "58") (name "SPI_MISO") (class "Default")
      (node (ref "JP1") (pin "18") (pinfunction "18_18") (pintype "passive"))
      (node (ref "JP2") (pin "18") (pinfunction "18_18") (pintype "passive"))
      (node (ref "JP_SPI_2") (pin "1") (pinfunction "1_1") (pintype "passive"))
      (node (ref "U$2") (pin "SO") (pinfunction "MISO_SO") (pintype "output"))
      (node (ref "U$5") (pin "MISO") (pinfunction "MISO_MISO") (pintype "bidirectional"))
      (node (ref "U$7") (pin "D13") (pinfunction "IO13_D13") (pintype "bidirectional"))
    )
    (net (code "59") (name "SPI_MOSI") (class "Default")
      (node (ref "JP1") (pin "16") (pinfunction "16_16") (pintype "passive"))
      (node (ref "JP2") (pin "16") (pinfunction "16_16") (pintype "passive"))
      (node (ref "JP_SPI_2") (pin "4") (pinfunction "4_4") (pintype "passive"))
      (node (ref "U$2") (pin "SI") (pinfunction "MOSI_SI") (pintype "input"))
      (node (ref "U$5") (pin "MOSI") (pinfunction "MOSI_MOSI") (pintype "bidirectional"))
      (node (ref "U$7") (pin "D12") (pinfunction "IO12_D12") (pintype "bidirectional"))
    )
    (net (code "60") (name "SPI_SCK") (class "Default")
      (node (ref "JP1") (pin "14") (pinfunction "14_14") (pintype "passive"))
      (node (ref "JP2") (pin "14") (pinfunction "14_14") (pintype "passive"))
      (node (ref "JP_SPI_2") (pin "3") (pinfunction "3_3") (pintype "passive"))
      (node (ref "U$2") (pin "SCK") (pinfunction "SCK_SCK") (pintype "input"))
      (node (ref "U$5") (pin "SCK") (pinfunction "SCK_SCK") (pintype "bidirectional"))
      (node (ref "U$7") (pin "D14") (pinfunction "IO14_D14") (pintype "bidirectional"))
    )
    (net (code "61") (name "UART0_RX") (class "Default")
      (node (ref "JP_UART1") (pin "2") (pinfunction "2_2") (pintype "passive"))
      (node (ref "U$7") (pin "D3") (pinfunction "IO3_D3") (pintype "bidirectional"))
    )
    (net (code "62") (name "UART0_TX") (class "Default")
      (node (ref "JP_UART1") (pin "3") (pinfunction "3_3") (pintype "passive"))
      (node (ref "U$7") (pin "D1") (pinfunction "IO1_D1") (pintype "bidirectional"))
    )
    (net (code "63") (name "UART2_RX") (class "Default")
      (node (ref "JP1") (pin "13") (pinfunction "13_13") (pintype "passive"))
      (node (ref "JP2") (pin "13") (pinfunction "13_13") (pintype "passive"))
      (node (ref "R16") (pin "2") (pinfunction "2_2") (pintype "passive"))
      (node (ref "R29") (pin "2") (pinfunction "2_2") (pintype "passive"))
      (node (ref "U$7") (pin "D16") (pinfunction "IO16_D16") (pintype "bidirectional"))
    )
    (net (code "64") (name "UART2_TX") (class "Default")
      (node (ref "JP1") (pin "11") (pinfunction "11_11") (pintype "passive"))
      (node (ref "JP2") (pin "11") (pinfunction "11_11") (pintype "passive"))
      (node (ref "Q1") (pin "S") (pinfunction "S_S") (pintype "passive"))
      (node (ref "R22") (pin "1") (pinfunction "1_1") (pintype "passive"))
      (node (ref "U$7") (pin "D17") (pinfunction "IO17_D17") (pintype "bidirectional"))
    )
    (net (code "65") (name "unconnected-(U$2-PadTERM_REST0)") (class "Default")
      (node (ref "U$2") (pin "TERM_REST0") (pinfunction "TERM_REST0_TERM_REST0") (pintype "bidirectional"))
    )
    (net (code "66") (name "unconnected-(U$2-PadTERM_REST1)") (class "Default")
      (node (ref "U$2") (pin "TERM_REST1") (pinfunction "TERM_REST1_TERM_REST1") (pintype "bidirectional"))
    )
    (net (code "67") (name "unconnected-(U$3-PadAD0)") (class "Default")
      (node (ref "U$3") (pin "AD0") (pinfunction "AD0_AD0") (pintype "bidirectional"))
    )
    (net (code "68") (name "unconnected-(U$3-PadECL)") (class "Default")
      (node (ref "U$3") (pin "ECL") (pinfunction "ECL_ECL") (pintype "bidirectional"))
    )
    (net (code "69") (name "unconnected-(U$3-PadEDA)") (class "Default")
      (node (ref "U$3") (pin "EDA") (pinfunction "EDA_EDA") (pintype "bidirectional"))
    )
    (net (code "70") (name "unconnected-(U$3-PadINT)") (class "Default")
      (node (ref "U$3") (pin "INT") (pinfunction "INT_INT") (pintype "bidirectional"))
    )
    (net (code "71") (name "unconnected-(U$3-PadNCS)") (class "Default")
      (node (ref "U$3") (pin "NCS") (pinfunction "NCS_NCS") (pintype "bidirectional"))
    )
    (net (code "72") (name "unconnected-(U$6-IO2{slash}CTS1-PadIO2)") (class "Default")
      (node (ref "U$6") (pin "IO2") (pinfunction "IO2/CTS1_IO2") (pintype "bidirectional"))
    )
    (net (code "73") (name "unconnected-(U$6-IO3{slash}RTS1-PadIO3)") (class "Default")
      (node (ref "U$6") (pin "IO3") (pinfunction "IO3/RTS1_IO3") (pintype "bidirectional"))
    )
    (net (code "74") (name "unconnected-(U$6-IO4{slash}RX2-PadIO4)") (class "Default")
      (node (ref "U$6") (pin "IO4") (pinfunction "IO4/RX2_IO4") (pintype "bidirectional"))
    )
    (net (code "75") (name "unconnected-(U$6-IO5{slash}TX2-PadIO5)") (class "Default")
      (node (ref "U$6") (pin "IO5") (pinfunction "IO5/TX2_IO5") (pintype "bidirectional"))
    )
    (net (code "76") (name "unconnected-(U$6-IO6{slash}CTS2-PadIO6)") (class "Default")
      (node (ref "U$6") (pin "IO6") (pinfunction "IO6/CTS2_IO6") (pintype "bidirectional"))
    )
    (net (code "77") (name "unconnected-(U$6-IO7{slash}RTS2-PadIO7)") (class "Default")
      (node (ref "U$6") (pin "IO7") (pinfunction "IO7/RTS2_IO7") (pintype "bidirectional"))
    )
    (net (code "78") (name "unconnected-(U$6-IO19{slash}I2C2_SCL-PadIO19)") (class "Default")
      (node (ref "U$6") (pin "IO19") (pinfunction "IO19/I2C2_SCL_IO19") (pintype "bidirectional"))
    )
    (net (code "79") (name "unconnected-(U$6-IO20{slash}I2C2_SDA-PadIO20)") (class "Default")
      (node (ref "U$6") (pin "IO20") (pinfunction "IO20/I2C2_SDA_IO20") (pintype "bidirectional"))
    )
    (net (code "80") (name "unconnected-(U$6-PadADC0)") (class "Default")
      (node (ref "U$6") (pin "ADC0") (pinfunction "ADC0_ADC0") (pintype "bidirectional"))
    )
    (net (code "81") (name "unconnected-(U$6-PadADC1)") (class "Default")
      (node (ref "U$6") (pin "ADC1") (pinfunction "ADC1_ADC1") (pintype "bidirectional"))
    )
    (net (code "82") (name "unconnected-(U$6-PadHST_RX)") (class "Default")
      (node (ref "U$6") (pin "HST_RX") (pinfunction "HST_RX_HST_RX") (pintype "bidirectional"))
    )
    (net (code "83") (name "unconnected-(U$6-PadHST_TX)") (class "Default")
      (node (ref "U$6") (pin "HST_TX") (pinfunction "HST_TX_HST_TX") (pintype "bidirectional"))
    )
    (net (code "84") (name "unconnected-(U$6-PadIO14)") (class "Default")
      (node (ref "U$6") (pin "IO14") (pinfunction "IO14_IO14") (pintype "bidirectional"))
    )
    (net (code "85") (name "unconnected-(U$6-PadIO15)") (class "Default")
      (node (ref "U$6") (pin "IO15") (pinfunction "IO15_IO15") (pintype "bidirectional"))
    )
    (net (code "86") (name "unconnected-(U$6-PadIO16)") (class "Default")
      (node (ref "U$6") (pin "IO16") (pinfunction "IO16_IO16") (pintype "bidirectional"))
    )
    (net (code "87") (name "unconnected-(U$6-PadIO17)") (class "Default")
      (node (ref "U$6") (pin "IO17") (pinfunction "IO17_IO17") (pintype "bidirectional"))
    )
    (net (code "88") (name "unconnected-(U$6-PadIO18)") (class "Default")
      (node (ref "U$6") (pin "IO18") (pinfunction "IO18_IO18") (pintype "bidirectional"))
    )
    (net (code "89") (name "unconnected-(U$6-PadIO25)") (class "Default")
      (node (ref "U$6") (pin "IO25") (pinfunction "IO25_IO25") (pintype "bidirectional"))
    )
    (net (code "90") (name "unconnected-(U$6-PadIO26)") (class "Default")
      (node (ref "U$6") (pin "IO26") (pinfunction "IO26_IO26") (pintype "bidirectional"))
    )
    (net (code "91") (name "unconnected-(U$6-PadIO29)") (class "Default")
      (node (ref "U$6") (pin "IO29") (pinfunction "IO29_IO29") (pintype "bidirectional"))
    )
    (net (code "92") (name "unconnected-(U$6-PadIO30)") (class "Default")
      (node (ref "U$6") (pin "IO30") (pinfunction "IO30_IO30") (pintype "bidirectional"))
    )
    (net (code "93") (name "unconnected-(U$6-PadPWR_KEY)") (class "Default")
      (node (ref "U$6") (pin "PWR_KEY") (pinfunction "PWR_KEY_PWR_KEY") (pintype "bidirectional"))
    )
    (net (code "94") (name "unconnected-(U$6-PadVBAT)") (class "Default")
      (node (ref "U$6") (pin "VBAT") (pinfunction "VBAT_VBAT") (pintype "bidirectional"))
    )
    (net (code "95") (name "unconnected-(U$6-PadVIO)") (class "Default")
      (node (ref "U$6") (pin "VIO") (pinfunction "VIO_VIO") (pintype "bidirectional"))
    )
  )
)
